# LT5560.net
KiCad netlist of a schematic drawn in EAGLE
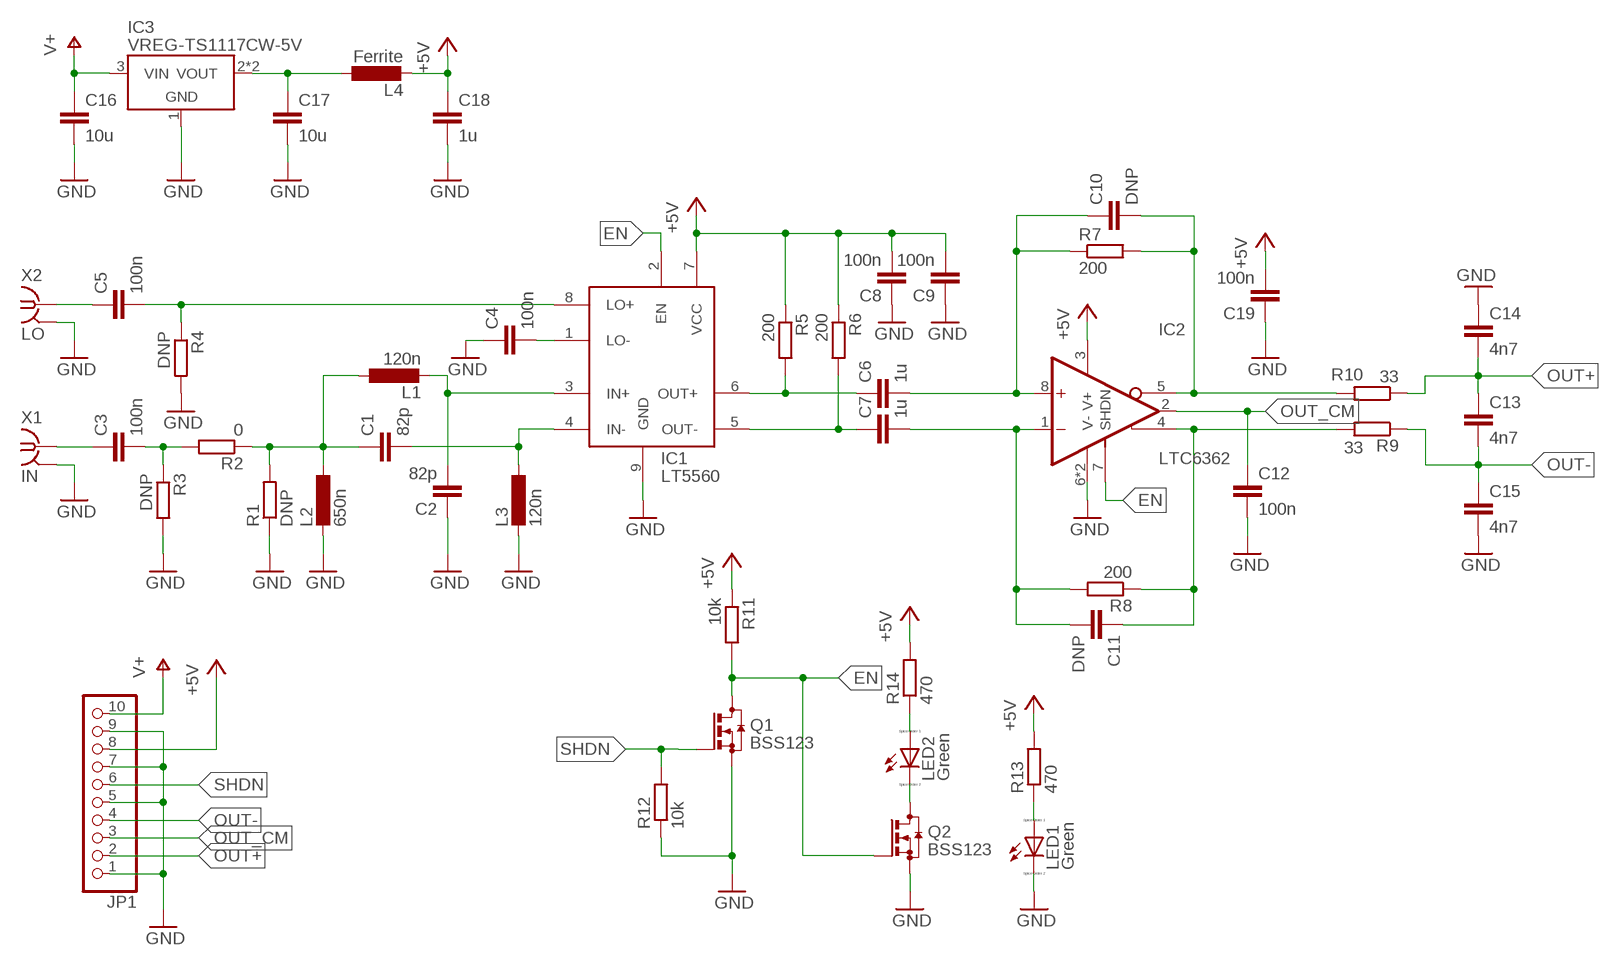
[diagram p0: schematic, sheet 1]

(export (version "E")
  (design (tool "Eeschema 10.0.6"))
  (components
    (comp (ref "C1")
      (value "82p")
      (footprint "eagle-import:C0603")
      (libsource (lib "eagle-import") (part "resistor_C-EUC0603"))
    )
    (comp (ref "C2")
      (value "82p")
      (footprint "eagle-import:C0603")
      (libsource (lib "eagle-import") (part "resistor_C-EUC0603"))
    )
    (comp (ref "C3")
      (value "100n")
      (footprint "eagle-import:C0603")
      (libsource (lib "eagle-import") (part "resistor_C-EUC0603"))
    )
    (comp (ref "C4")
      (value "100n")
      (footprint "eagle-import:C0603")
      (libsource (lib "eagle-import") (part "resistor_C-EUC0603"))
    )
    (comp (ref "C5")
      (value "100n")
      (footprint "eagle-import:C0603")
      (libsource (lib "eagle-import") (part "resistor_C-EUC0603"))
    )
    (comp (ref "C6")
      (value "1u")
      (footprint "eagle-import:C0603")
      (libsource (lib "eagle-import") (part "resistor_C-EUC0603"))
    )
    (comp (ref "C7")
      (value "1u")
      (footprint "eagle-import:C0603")
      (libsource (lib "eagle-import") (part "resistor_C-EUC0603"))
    )
    (comp (ref "C8")
      (value "100n")
      (footprint "eagle-import:C0603")
      (libsource (lib "eagle-import") (part "resistor_C-EUC0603"))
    )
    (comp (ref "C9")
      (value "100n")
      (footprint "eagle-import:C0603")
      (libsource (lib "eagle-import") (part "resistor_C-EUC0603"))
    )
    (comp (ref "C10")
      (value "DNP")
      (footprint "eagle-import:C0603")
      (libsource (lib "eagle-import") (part "resistor_C-EUC0603"))
    )
    (comp (ref "C11")
      (value "DNP")
      (footprint "eagle-import:C0603")
      (libsource (lib "eagle-import") (part "resistor_C-EUC0603"))
    )
    (comp (ref "C12")
      (value "100n")
      (footprint "eagle-import:C0603")
      (libsource (lib "eagle-import") (part "resistor_C-EUC0603"))
    )
    (comp (ref "C13")
      (value "4n7")
      (footprint "eagle-import:C0603")
      (libsource (lib "eagle-import") (part "resistor_C-EUC0603"))
    )
    (comp (ref "C14")
      (value "4n7")
      (footprint "eagle-import:C0603")
      (libsource (lib "eagle-import") (part "resistor_C-EUC0603"))
    )
    (comp (ref "C15")
      (value "4n7")
      (footprint "eagle-import:C0603")
      (libsource (lib "eagle-import") (part "resistor_C-EUC0603"))
    )
    (comp (ref "C16")
      (value "10u")
      (footprint "eagle-import:C1206")
      (libsource (lib "eagle-import") (part "C-EUC1206"))
    )
    (comp (ref "C17")
      (value "10u")
      (footprint "eagle-import:C1206")
      (libsource (lib "eagle-import") (part "C-EUC1206"))
    )
    (comp (ref "C18")
      (value "1u")
      (footprint "eagle-import:C0603")
      (libsource (lib "eagle-import") (part "C-EUC0603"))
    )
    (comp (ref "C19")
      (value "100n")
      (footprint "eagle-import:C0603")
      (libsource (lib "eagle-import") (part "resistor_C-EUC0603"))
    )
    (comp (ref "IC1")
      (value "LT5560")
      (footprint "eagle-import:SON50P300X300X80-9T165X238")
      (libsource (lib "eagle-import") (part "LT5560"))
    )
    (comp (ref "IC2")
      (value "LTC6362")
      (footprint "eagle-import:SON50P300X300X80-9T165X238")
      (libsource (lib "eagle-import") (part "LTC6362"))
    )
    (comp (ref "IC3")
      (value "VREG-TS1117CW-5V")
      (footprint "eagle-import:SOT223")
      (libsource (lib "eagle-import") (part "VREG-TS1117CW-5V"))
    )
    (comp (ref "JP1")
      (value "PINHD-1X10/90")
      (footprint "eagle-import:1X10_90")
      (libsource (lib "eagle-import") (part "PINHD-1X10/90"))
    )
    (comp (ref "L1")
      (value "120n")
      (footprint "eagle-import:R0603")
      (libsource (lib "eagle-import") (part "INDUCTOR0603"))
    )
    (comp (ref "L2")
      (value "650n")
      (footprint "eagle-import:R0603")
      (libsource (lib "eagle-import") (part "INDUCTOR0603"))
    )
    (comp (ref "L3")
      (value "120n")
      (footprint "eagle-import:R0603")
      (libsource (lib "eagle-import") (part "INDUCTOR0603"))
    )
    (comp (ref "L4")
      (value "Ferrite")
      (footprint "eagle-import:R0603")
      (libsource (lib "eagle-import") (part "INDUCTOR0603"))
    )
    (comp (ref "LED1")
      (value "Green")
      (footprint "eagle-import:LED_SML0603")
      (libsource (lib "eagle-import") (part "LED_ESML0603"))
    )
    (comp (ref "LED2")
      (value "Green")
      (footprint "eagle-import:LED_SML0603")
      (libsource (lib "eagle-import") (part "LED_ESML0603"))
    )
    (comp (ref "Q1")
      (value "BSS123")
      (footprint "eagle-import:SOT23")
      (libsource (lib "eagle-import") (part "BSS123"))
    )
    (comp (ref "Q2")
      (value "BSS123")
      (footprint "eagle-import:SOT23")
      (libsource (lib "eagle-import") (part "BSS123"))
    )
    (comp (ref "R1")
      (value "DNP")
      (footprint "eagle-import:R0603")
      (libsource (lib "eagle-import") (part "R-EU_R0603"))
    )
    (comp (ref "R2")
      (value "0")
      (footprint "eagle-import:R0603")
      (libsource (lib "eagle-import") (part "R-EU_R0603"))
    )
    (comp (ref "R3")
      (value "DNP")
      (footprint "eagle-import:R0603")
      (libsource (lib "eagle-import") (part "R-EU_R0603"))
    )
    (comp (ref "R4")
      (value "DNP")
      (footprint "eagle-import:R0603")
      (libsource (lib "eagle-import") (part "R-EU_R0603"))
    )
    (comp (ref "R5")
      (value "200")
      (footprint "eagle-import:R0603")
      (libsource (lib "eagle-import") (part "R-EU_R0603"))
    )
    (comp (ref "R6")
      (value "200")
      (footprint "eagle-import:R0603")
      (libsource (lib "eagle-import") (part "R-EU_R0603"))
    )
    (comp (ref "R7")
      (value "200")
      (footprint "eagle-import:R0603")
      (libsource (lib "eagle-import") (part "R-EU_R0603"))
    )
    (comp (ref "R8")
      (value "200")
      (footprint "eagle-import:R0603")
      (libsource (lib "eagle-import") (part "R-EU_R0603"))
    )
    (comp (ref "R9")
      (value "33")
      (footprint "eagle-import:R0603")
      (libsource (lib "eagle-import") (part "R-EU_R0603"))
    )
    (comp (ref "R10")
      (value "33")
      (footprint "eagle-import:R0603")
      (libsource (lib "eagle-import") (part "R-EU_R0603"))
    )
    (comp (ref "R11")
      (value "10k")
      (footprint "eagle-import:R0603")
      (libsource (lib "eagle-import") (part "R-EU_R0603"))
    )
    (comp (ref "R12")
      (value "10k")
      (footprint "eagle-import:R0603")
      (libsource (lib "eagle-import") (part "R-EU_R0603"))
    )
    (comp (ref "R13")
      (value "470")
      (footprint "eagle-import:R0603")
      (libsource (lib "eagle-import") (part "resistor_R-EU_R0603"))
    )
    (comp (ref "R14")
      (value "470")
      (footprint "eagle-import:R0603")
      (libsource (lib "eagle-import") (part "resistor_R-EU_R0603"))
    )
    (comp (ref "X1")
      (value "IN")
      (footprint "eagle-import:J502-ND-142-0711-821_826")
      (libsource (lib "eagle-import") (part "SMA_CONNECTOR"))
    )
    (comp (ref "X2")
      (value "LO")
      (footprint "eagle-import:J502-ND-142-0711-821_826")
      (libsource (lib "eagle-import") (part "SMA_CONNECTOR"))
    )
  )
  (nets
    (net (code "1") (name "+5V") (class "Default")
      (node (ref "C18") (pin "1") (pinfunction "1_1") (pintype "passive"))
      (node (ref "C19") (pin "2") (pinfunction "2_2") (pintype "passive"))
      (node (ref "C8") (pin "2") (pinfunction "2_2") (pintype "passive"))
      (node (ref "C9") (pin "2") (pinfunction "2_2") (pintype "passive"))
      (node (ref "IC1") (pin "7") (pinfunction "VCC_7") (pintype "bidirectional"))
      (node (ref "IC2") (pin "3") (pinfunction "V+_3") (pintype "power_in"))
      (node (ref "JP1") (pin "8") (pinfunction "8_8") (pintype "passive"))
      (node (ref "L4") (pin "2") (pinfunction "2_2") (pintype "passive"))
      (node (ref "R11") (pin "1") (pinfunction "1_1") (pintype "passive"))
      (node (ref "R13") (pin "2") (pinfunction "2_2") (pintype "passive"))
      (node (ref "R14") (pin "2") (pinfunction "2_2") (pintype "passive"))
      (node (ref "R5") (pin "1") (pinfunction "1_1") (pintype "passive"))
      (node (ref "R6") (pin "1") (pinfunction "1_1") (pintype "passive"))
    )
    (net (code "2") (name "EN") (class "Default")
      (node (ref "IC1") (pin "2") (pinfunction "EN_2") (pintype "bidirectional"))
      (node (ref "IC2") (pin "7") (pinfunction "SHDN_7") (pintype "bidirectional"))
      (node (ref "Q1") (pin "3") (pinfunction "D_3") (pintype "passive"))
      (node (ref "Q2") (pin "1") (pinfunction "G_1") (pintype "passive"))
      (node (ref "R11") (pin "2") (pinfunction "2_2") (pintype "passive"))
    )
    (net (code "3") (name "GND") (class "Default")
      (node (ref "C12") (pin "2") (pinfunction "2_2") (pintype "passive"))
      (node (ref "C14") (pin "1") (pinfunction "1_1") (pintype "passive"))
      (node (ref "C15") (pin "2") (pinfunction "2_2") (pintype "passive"))
      (node (ref "C16") (pin "2") (pinfunction "2_2") (pintype "passive"))
      (node (ref "C17") (pin "2") (pinfunction "2_2") (pintype "passive"))
      (node (ref "C18") (pin "2") (pinfunction "2_2") (pintype "passive"))
      (node (ref "C19") (pin "1") (pinfunction "1_1") (pintype "passive"))
      (node (ref "C2") (pin "1") (pinfunction "1_1") (pintype "passive"))
      (node (ref "C4") (pin "1") (pinfunction "1_1") (pintype "passive"))
      (node (ref "C8") (pin "1") (pinfunction "1_1") (pintype "passive"))
      (node (ref "C9") (pin "1") (pinfunction "1_1") (pintype "passive"))
      (node (ref "IC1") (pin "9") (pinfunction "GND_9") (pintype "bidirectional"))
      (node (ref "IC2") (pin "6") (pinfunction "V-_6") (pintype "power_in"))
      (node (ref "IC2") (pin "9") (pinfunction "V-_9") (pintype "power_in"))
      (node (ref "IC3") (pin "1") (pinfunction "GND_1") (pintype "power_in"))
      (node (ref "JP1") (pin "1") (pinfunction "1_1") (pintype "passive"))
      (node (ref "JP1") (pin "5") (pinfunction "5_5") (pintype "passive"))
      (node (ref "JP1") (pin "7") (pinfunction "7_7") (pintype "passive"))
      (node (ref "JP1") (pin "9") (pinfunction "9_9") (pintype "passive"))
      (node (ref "L2") (pin "2") (pinfunction "2_2") (pintype "passive"))
      (node (ref "L3") (pin "2") (pinfunction "2_2") (pintype "passive"))
      (node (ref "LED1") (pin "C") (pinfunction "C_C") (pintype "passive"))
      (node (ref "Q1") (pin "2") (pinfunction "S_2") (pintype "passive"))
      (node (ref "Q2") (pin "2") (pinfunction "S_2") (pintype "passive"))
      (node (ref "R1") (pin "1") (pinfunction "1_1") (pintype "passive"))
      (node (ref "R12") (pin "1") (pinfunction "1_1") (pintype "passive"))
      (node (ref "R3") (pin "2") (pinfunction "2_2") (pintype "passive"))
      (node (ref "R4") (pin "2") (pinfunction "2_2") (pintype "passive"))
      (node (ref "X1") (pin "G@1") (pinfunction "2_G@1") (pintype "passive"))
      (node (ref "X1") (pin "G@2") (pinfunction "2_G@2") (pintype "passive"))
      (node (ref "X1") (pin "G@3") (pinfunction "2_G@3") (pintype "passive"))
      (node (ref "X1") (pin "G@4") (pinfunction "2_G@4") (pintype "passive"))
      (node (ref "X2") (pin "G@1") (pinfunction "2_G@1") (pintype "passive"))
      (node (ref "X2") (pin "G@2") (pinfunction "2_G@2") (pintype "passive"))
      (node (ref "X2") (pin "G@3") (pinfunction "2_G@3") (pintype "passive"))
      (node (ref "X2") (pin "G@4") (pinfunction "2_G@4") (pintype "passive"))
    )
    (net (code "4") (name "Net-(C1-Pad1)") (class "Default")
      (node (ref "C1") (pin "1") (pinfunction "1_1") (pintype "passive"))
      (node (ref "L1") (pin "1") (pinfunction "1_1") (pintype "passive"))
      (node (ref "L2") (pin "1") (pinfunction "1_1") (pintype "passive"))
      (node (ref "R1") (pin "2") (pinfunction "2_2") (pintype "passive"))
      (node (ref "R2") (pin "1") (pinfunction "1_1") (pintype "passive"))
    )
    (net (code "5") (name "Net-(C3-Pad1)") (class "Default")
      (node (ref "C3") (pin "1") (pinfunction "1_1") (pintype "passive"))
      (node (ref "X1") (pin "1") (pinfunction "1_1") (pintype "passive"))
    )
    (net (code "6") (name "Net-(C3-Pad2)") (class "Default")
      (node (ref "C3") (pin "2") (pinfunction "2_2") (pintype "passive"))
      (node (ref "R2") (pin "2") (pinfunction "2_2") (pintype "passive"))
      (node (ref "R3") (pin "1") (pinfunction "1_1") (pintype "passive"))
    )
    (net (code "7") (name "Net-(C5-Pad1)") (class "Default")
      (node (ref "C5") (pin "1") (pinfunction "1_1") (pintype "passive"))
      (node (ref "X2") (pin "1") (pinfunction "1_1") (pintype "passive"))
    )
    (net (code "8") (name "Net-(C17-Pad1)") (class "Default")
      (node (ref "C17") (pin "1") (pinfunction "1_1") (pintype "passive"))
      (node (ref "IC3") (pin "2") (pinfunction "VOUT_2") (pintype "power_in"))
      (node (ref "IC3") (pin "4") (pinfunction "VOUT_4") (pintype "power_in"))
      (node (ref "L4") (pin "1") (pinfunction "1_1") (pintype "passive"))
    )
    (net (code "9") (name "Net-(IC1-IN+)") (class "Default")
      (node (ref "C2") (pin "2") (pinfunction "2_2") (pintype "passive"))
      (node (ref "IC1") (pin "3") (pinfunction "IN+_3") (pintype "bidirectional"))
      (node (ref "L1") (pin "2") (pinfunction "2_2") (pintype "passive"))
    )
    (net (code "10") (name "Net-(IC1-IN-)") (class "Default")
      (node (ref "C1") (pin "2") (pinfunction "2_2") (pintype "passive"))
      (node (ref "IC1") (pin "4") (pinfunction "IN-_4") (pintype "bidirectional"))
      (node (ref "L3") (pin "1") (pinfunction "1_1") (pintype "passive"))
    )
    (net (code "11") (name "Net-(IC1-LO+)") (class "Default")
      (node (ref "C5") (pin "2") (pinfunction "2_2") (pintype "passive"))
      (node (ref "IC1") (pin "8") (pinfunction "LO+_8") (pintype "bidirectional"))
      (node (ref "R4") (pin "1") (pinfunction "1_1") (pintype "passive"))
    )
    (net (code "12") (name "Net-(IC1-LO-)") (class "Default")
      (node (ref "C4") (pin "2") (pinfunction "2_2") (pintype "passive"))
      (node (ref "IC1") (pin "1") (pinfunction "LO-_1") (pintype "bidirectional"))
    )
    (net (code "13") (name "Net-(IC1-OUT+)") (class "Default")
      (node (ref "C6") (pin "1") (pinfunction "1_1") (pintype "passive"))
      (node (ref "IC1") (pin "6") (pinfunction "OUT+_6") (pintype "bidirectional"))
      (node (ref "R5") (pin "2") (pinfunction "2_2") (pintype "passive"))
    )
    (net (code "14") (name "Net-(IC1-OUT-)") (class "Default")
      (node (ref "C7") (pin "1") (pinfunction "1_1") (pintype "passive"))
      (node (ref "IC1") (pin "5") (pinfunction "OUT-_5") (pintype "bidirectional"))
      (node (ref "R6") (pin "2") (pinfunction "2_2") (pintype "passive"))
    )
    (net (code "15") (name "Net-(IC2-+IN)") (class "Default")
      (node (ref "C10") (pin "1") (pinfunction "1_1") (pintype "passive"))
      (node (ref "C6") (pin "2") (pinfunction "2_2") (pintype "passive"))
      (node (ref "IC2") (pin "8") (pinfunction "+IN_8") (pintype "input"))
      (node (ref "R7") (pin "1") (pinfunction "1_1") (pintype "passive"))
    )
    (net (code "16") (name "Net-(IC2-+OUT)") (class "Default")
      (node (ref "C11") (pin "1") (pinfunction "1_1") (pintype "passive"))
      (node (ref "IC2") (pin "4") (pinfunction "+OUT_4") (pintype "bidirectional"))
      (node (ref "R8") (pin "1") (pinfunction "1_1") (pintype "passive"))
      (node (ref "R9") (pin "2") (pinfunction "2_2") (pintype "passive"))
    )
    (net (code "17") (name "Net-(IC2--IN)") (class "Default")
      (node (ref "C11") (pin "2") (pinfunction "2_2") (pintype "passive"))
      (node (ref "C7") (pin "2") (pinfunction "2_2") (pintype "passive"))
      (node (ref "IC2") (pin "1") (pinfunction "-IN_1") (pintype "input"))
      (node (ref "R8") (pin "2") (pinfunction "2_2") (pintype "passive"))
    )
    (net (code "18") (name "Net-(IC2--OUT)") (class "Default")
      (node (ref "C10") (pin "2") (pinfunction "2_2") (pintype "passive"))
      (node (ref "IC2") (pin "5") (pinfunction "-OUT_5") (pintype "bidirectional"))
      (node (ref "R10") (pin "2") (pinfunction "2_2") (pintype "passive"))
      (node (ref "R7") (pin "2") (pinfunction "2_2") (pintype "passive"))
    )
    (net (code "19") (name "Net-(LED1-PadA)") (class "Default")
      (node (ref "LED1") (pin "A") (pinfunction "A_A") (pintype "passive"))
      (node (ref "R13") (pin "1") (pinfunction "1_1") (pintype "passive"))
    )
    (net (code "20") (name "Net-(LED2-PadA)") (class "Default")
      (node (ref "LED2") (pin "A") (pinfunction "A_A") (pintype "passive"))
      (node (ref "R14") (pin "1") (pinfunction "1_1") (pintype "passive"))
    )
    (net (code "21") (name "Net-(Q2-D)") (class "Default")
      (node (ref "LED2") (pin "C") (pinfunction "C_C") (pintype "passive"))
      (node (ref "Q2") (pin "3") (pinfunction "D_3") (pintype "passive"))
    )
    (net (code "22") (name "OUT+") (class "Default")
      (node (ref "C13") (pin "1") (pinfunction "1_1") (pintype "passive"))
      (node (ref "C14") (pin "2") (pinfunction "2_2") (pintype "passive"))
      (node (ref "JP1") (pin "2") (pinfunction "2_2") (pintype "passive"))
      (node (ref "R10") (pin "1") (pinfunction "1_1") (pintype "passive"))
    )
    (net (code "23") (name "OUT-") (class "Default")
      (node (ref "C13") (pin "2") (pinfunction "2_2") (pintype "passive"))
      (node (ref "C15") (pin "1") (pinfunction "1_1") (pintype "passive"))
      (node (ref "JP1") (pin "4") (pinfunction "4_4") (pintype "passive"))
      (node (ref "R9") (pin "1") (pinfunction "1_1") (pintype "passive"))
    )
    (net (code "24") (name "OUT_CM") (class "Default")
      (node (ref "C12") (pin "1") (pinfunction "1_1") (pintype "passive"))
      (node (ref "IC2") (pin "2") (pinfunction "VOCM_2") (pintype "output"))
      (node (ref "JP1") (pin "3") (pinfunction "3_3") (pintype "passive"))
    )
    (net (code "25") (name "SHDN") (class "Default")
      (node (ref "JP1") (pin "6") (pinfunction "6_6") (pintype "passive"))
      (node (ref "Q1") (pin "1") (pinfunction "G_1") (pintype "passive"))
      (node (ref "R12") (pin "2") (pinfunction "2_2") (pintype "passive"))
    )
    (net (code "26") (name "V+") (class "Default")
      (node (ref "C16") (pin "1") (pinfunction "1_1") (pintype "passive"))
      (node (ref "IC3") (pin "3") (pinfunction "VIN_3") (pintype "power_in"))
      (node (ref "JP1") (pin "10") (pinfunction "10_10") (pintype "passive"))
    )
  )
)
